# Beacon.net
KiCad netlist of a schematic drawn in Altium Designer
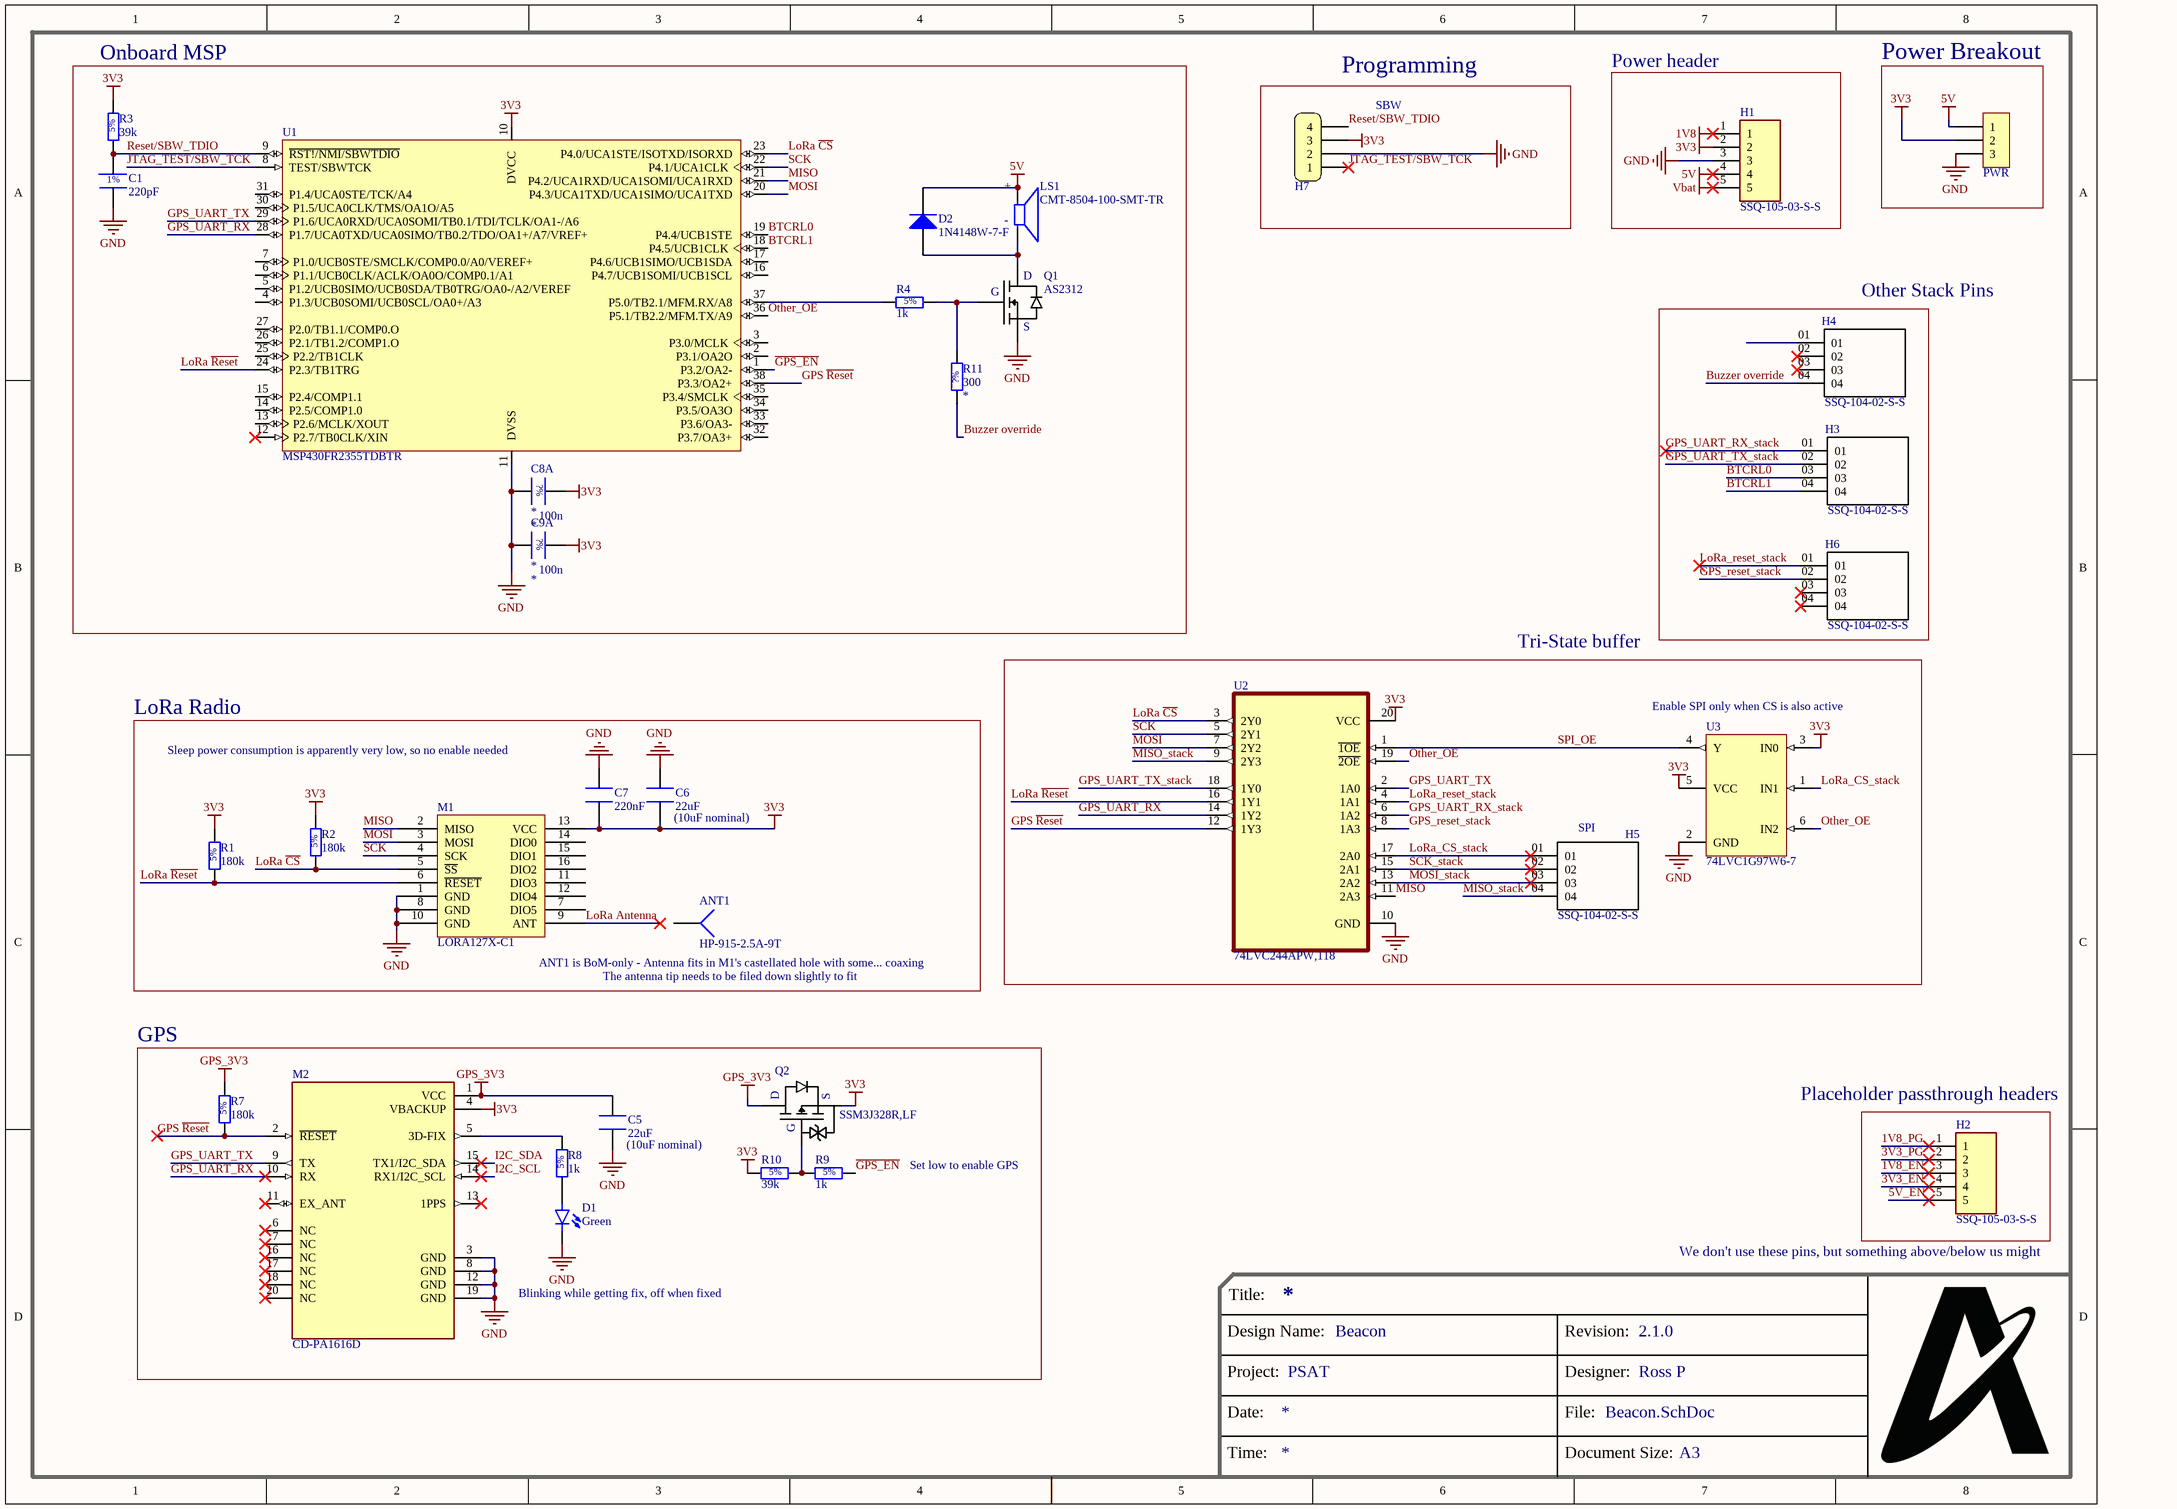
[diagram p0: Beacon.SchDoc]

(export (version "E")
  (design (tool "Eeschema 10.0.6"))
  (components
    (comp (ref "ANT1")
      (value "HP-915-2.5A-9T")
      (description "Spring Antenna")
      (libsource (lib "Miscellaneous Connectors") (part "Socket"))
    )
    (comp (ref "C1")
      (value "220pF")
      (footprint "APSS Prototype Parts:CAPACITOR_0805_2012M-70N")
      (description "Passive - Capacitor Series, C0G, 5pF ~ 22nF, 50V, 0805 (2012 Metric), ±1%, -55°C ~ 125°C")
      (fields (field (name "TOLERANCE") "±1%") (field (name "APSS STANDARD PART") "APSS Standard"))
      (libsource (lib "APSS Prototype Parts") (part "GCM2165CxxxxxF Series"))
    )
    (comp (ref "C5")
      (value "22uF")
      (footprint "APSS Prototype Parts:CAPACITOR_0805_2012M-70N")
      (description "Passive - Capacitor, X5R, 22uF Max, 6.3V, 0805 (2012 Metric), ±20%, -55°C ~ 85°C. 8.8uF @ 5V")
      (fields (field (name "TOLERANCE") "±20%") (field (name "MF PART NO.") "C0805C226M9PACTU"))
      (libsource (lib "APSS Prototype Parts") (part "C0805C226M9PACTU"))
    )
    (comp (ref "C6")
      (value "22uF")
      (footprint "APSS Prototype Parts:CAPACITOR_0805_2012M-70N")
      (description "Passive - Capacitor, X5R, 22uF Max, 6.3V, 0805 (2012 Metric), ±20%, -55°C ~ 85°C. 8.8uF @ 5V")
      (fields (field (name "TOLERANCE") "±20%") (field (name "MF PART NO.") "C0805C226M9PACTU"))
      (libsource (lib "APSS Prototype Parts") (part "C0805C226M9PACTU"))
    )
    (comp (ref "C7")
      (value "220nF")
      (footprint "APSS Prototype Parts:CAPACITOR_0805_2012M-70N")
      (fields
        (field (name "TOLERANCE") "±10%")
        (field (name "MF PART NO.") "C0805C224K1RAC7800")
        (field (name "APSS STANDARD PART") "APSS Standard")
      )
      (libsource (lib "APSS Prototype Parts") (part "C0805C224K1RAC7800"))
    )
    (comp (ref "C8")
      (value "100n")
      (footprint "CAPACITOR_0805_2012M-70N")
      (description "Passive - Capacitor, Generic")
      (fields
        (field (name "TOLERANCE") "?%")
        (field (name "MF PART NO.") "*")
        (field (name "ALTIUM_VALUE") "*")
      )
      (libsource (lib "APSS Generic Components") (part "Generic Capacitor"))
    )
    (comp (ref "C9")
      (value "100n")
      (footprint "CAPACITOR_0805_2012M-70N")
      (description "Passive - Capacitor, Generic")
      (fields
        (field (name "TOLERANCE") "?%")
        (field (name "MF PART NO.") "*")
        (field (name "ALTIUM_VALUE") "*")
      )
      (libsource (lib "APSS Generic Components") (part "Generic Capacitor"))
    )
    (comp (ref "D1")
      (value "LTST-C190 Series")
      (footprint "APSS Prototype Parts:LED_0603_1608M_0.80mm")
      (description "Diode - LED, 0603")
      (fields
        (field (name "MF PART NO.") "LTST-C190KGKT")
        (field (name "COLOUR") "Green")
        (field (name "APSS STANDARD PART") "APSS Standard")
      )
      (libsource (lib "APSS Prototype Parts") (part "LTST-C190 Series"))
    )
    (comp (ref "D2")
      (value "1N4148W-7-F")
      (footprint "SOD123")
      (description "DIODE GEN PURP 100V 300MA SOD123")
      (fields
        (field (name "MANUFACTURER") "Diodes Incorporated")
        (field (name "MANUFACTURER PART NUMBER") "1N4148W-13-F")
      )
      (libsource (lib "EE209_Library") (part "1N4148_SMT_SOD123"))
    )
    (comp (ref "H1")
      (value "SSQ-105-03-S-S")
      (footprint "SAMTEC_SSQ-105-03-S-S:SAMTEC_SSQ-105-03-S-S")
      (libsource (lib "SSQ-105-03-S-S") (part "SSQ-105-03-S-S"))
    )
    (comp (ref "H2")
      (value "SSQ-105-03-S-S")
      (footprint "SAMTEC_SSQ-105-03-S-S:SAMTEC_SSQ-105-03-S-S")
      (libsource (lib "SSQ-105-03-S-S") (part "SSQ-105-03-S-S"))
    )
    (comp (ref "H3")
      (value "SSQ-104-02-S-S")
      (footprint "*SAMTEC_SSQ-104-02-S-S_SSQ-104-02-S-S(Primary)")
      (libsource (lib "SSQ-104-02-S-S") (part "SSQ-104-02-S-S"))
    )
    (comp (ref "H4")
      (value "SSQ-104-02-S-S")
      (footprint "*SAMTEC_SSQ-104-02-S-S_SSQ-104-02-S-S(Primary)")
      (libsource (lib "SSQ-104-02-S-S") (part "SSQ-104-02-S-S"))
    )
    (comp (ref "H5")
      (value "SSQ-104-02-S-S")
      (footprint "*SAMTEC_SSQ-104-02-S-S_SSQ-104-02-S-S(Primary)")
      (libsource (lib "SSQ-104-02-S-S") (part "SSQ-104-02-S-S"))
    )
    (comp (ref "H6")
      (value "SSQ-104-02-S-S")
      (footprint "*SAMTEC_SSQ-104-02-S-S_SSQ-104-02-S-S(Primary)")
      (libsource (lib "SSQ-104-02-S-S") (part "SSQ-104-02-S-S"))
    )
    (comp (ref "H7")
      (value "Headerless Pogo Holes 4-pin")
      (footprint "APSS Generic Components:POGO_4_PIN_HEADER")
      (libsource (lib "APSS Generic Components") (part "Headerless Pogo Holes 4-pin"))
    )
    (comp (ref "LS1")
      (value "CMT-8504-100-SMT-TR")
      (footprint "XDCR_CMT-8504-100-SMT-TR")
      (description "8.5 mm, 5 Vo-p, 100 dB, Surface Mount (SMT), Magnetic Audio Transducer Buzzer")
      (libsource (lib "CMT-8504-100-SMT-TR") (part "CMT-8504-100-SMT-TR"))
    )
    (comp (ref "M1")
      (value "LORA127X-C1")
      (footprint "LoRa127X-C1")
      (description "LoRa transceiver")
      (libsource (lib "LORA127X-C1") (part "LORA127X-C1"))
    )
    (comp (ref "M2")
      (value "CD-PA1616D")
      (footprint "XCVR_CD-PA1616D")
      (description "CD-PA1616D GNSS patch antenna module")
      (libsource (lib "CD-PA1616D") (part "CD-PA1616D"))
    )
    (comp (ref "PWR")
      (value "HDR,2.54mm,1x3")
      (footprint "APSS Connectors:HEADER_2.54MM_1x3PIN")
      (description "Connector - 2.54mm, 1x3-pin")
      (libsource (lib "APSS Connectors") (part "HDR,2.54mm,1x3"))
    )
    (comp (ref "Q1")
      (value "AS2312")
      (footprint "APSS Prototype Parts:SOT23-3N-1.15mm")
      (description "Transistor - MOSFET, N-Channel AS2312")
      (fields (field (name "POWER") "1.2W") (field (name "APSS STANDARD PART") "APSS Standard"))
      (libsource (lib "APSS Prototype Parts") (part "AS2312"))
    )
    (comp (ref "Q2")
      (value "SSM3J328R,LF")
      (footprint "APSS Prototype Parts:SOT23F-3-0.8mm")
      (description "Transistor - MOSFET, P-Channel SSM3J328R,LF")
      (fields (field (name "POWER") "1W") (field (name "APSS STANDARD PART") "APSS Standard"))
      (libsource (lib "APSS Prototype Parts") (part "SSM3J328R,LF"))
    )
    (comp (ref "R1")
      (value "180k")
      (footprint "APSS Prototype Parts:Resistor_0805_2012M-50N")
      (fields
        (field (name "TOLERANCE") "5%")
        (field (name "POWER") "1/8W")
        (field (name "MF PART NO.") "RMCF0805JT180K")
      )
      (libsource (lib "APSS Prototype Parts") (part "RMCF0805JT Series"))
    )
    (comp (ref "R2")
      (value "180k")
      (footprint "APSS Prototype Parts:Resistor_0805_2012M-50N")
      (fields
        (field (name "TOLERANCE") "5%")
        (field (name "POWER") "1/8W")
        (field (name "MF PART NO.") "RMCF0805JT180K")
      )
      (libsource (lib "APSS Prototype Parts") (part "RMCF0805JT Series"))
    )
    (comp (ref "R3")
      (value "39k")
      (footprint "APSS Prototype Parts:Resistor_0805_2012M-50N")
      (fields
        (field (name "TOLERANCE") "5%")
        (field (name "POWER") "1/8W")
        (field (name "MF PART NO.") "RMCF0805JT39K0")
      )
      (libsource (lib "APSS Prototype Parts") (part "RMCF0805JT Series"))
    )
    (comp (ref "R4")
      (value "1k")
      (footprint "APSS Prototype Parts:Resistor_0805_2012M-50N")
      (fields
        (field (name "TOLERANCE") "5%")
        (field (name "POWER") "1/8W")
        (field (name "MF PART NO.") "RMCF0805JT1K00")
      )
      (libsource (lib "") (part "RMCF0805JT Series_1"))
    )
    (comp (ref "R7")
      (value "180k")
      (footprint "APSS Prototype Parts:Resistor_0805_2012M-50N")
      (fields
        (field (name "TOLERANCE") "5%")
        (field (name "POWER") "1/8W")
        (field (name "MF PART NO.") "RMCF0805JT180K")
      )
      (libsource (lib "APSS Prototype Parts") (part "RMCF0805JT Series"))
    )
    (comp (ref "R8")
      (value "1k")
      (footprint "APSS Prototype Parts:Resistor_0805_2012M-50N")
      (fields
        (field (name "TOLERANCE") "5%")
        (field (name "POWER") "1/8W")
        (field (name "MF PART NO.") "RMCF0805JT1K00")
      )
      (libsource (lib "APSS Prototype Parts") (part "RMCF0805JT Series"))
    )
    (comp (ref "R9")
      (value "1k")
      (footprint "APSS Prototype Parts:Resistor_0805_2012M-50N")
      (fields
        (field (name "TOLERANCE") "5%")
        (field (name "POWER") "1/8W")
        (field (name "MF PART NO.") "RMCF0805JT1K00")
      )
      (libsource (lib "") (part "RMCF0805JT Series_1"))
    )
    (comp (ref "R10")
      (value "39k")
      (footprint "APSS Prototype Parts:Resistor_0805_2012M-50N")
      (fields
        (field (name "TOLERANCE") "5%")
        (field (name "POWER") "1/8W")
        (field (name "MF PART NO.") "RMCF0805JT39K0")
      )
      (libsource (lib "") (part "RMCF0805JT Series_1"))
    )
    (comp (ref "R11")
      (value "300")
      (footprint "RESISTOR_0805_2012M-50N")
      (description "Passive - Resistor, Generic")
      (fields (field (name "TOLERANCE") "?%") (field (name "MF PART NO.") "*"))
      (libsource (lib "APSS Generic Components") (part "Generic Resistor"))
    )
    (comp (ref "U1")
      (value "MSP430FR2355TDBTR")
      (footprint "APSS Prototype Parts:TSSOP65P640X120-0.5mm-38N")
      (fields
        (field (name "MF PART NO.") "MSP430FR2355TPT")
        (field (name "APSS STANDARD PART") "APSS Standard")
      )
      (libsource (lib "APSS Prototype Parts") (part "MSP430FR2355TDBTR"))
    )
    (comp (ref "U2")
      (value "74LVC244APW,118")
      (footprint "SOP65P640X110-20N:SOP65P640X110-20N")
      (description "Octal buffer/line driver")
      (fields (field (name "MP") "74LVC244APW-118"))
      (libsource (lib "74LVC244APW,118") (part "74LVC244APW,118"))
    )
    (comp (ref "U3")
      (value "74LVC1G97W6-7")
      (footprint "APSS Prototype Parts:SOT23-6N-1.4mm")
      (description "IC - Multifunction Logic Gate, 1 Circuit, 3 Input, 1.65 - 5.5V, AND, OR, NOT, MUX, SOT-23-6")
      (fields (field (name "APSS STANDARD PART") "APSS Standard"))
      (libsource (lib "APSS Prototype Parts") (part "74LVC1G97W6-7"))
    )
  )
  (nets
    (net (code "1") (name "/1V8_EN") (class "Default")
      (node (ref "H2") (pin "3") (pinfunction "3_3") (pintype "passive+no_connect"))
    )
    (net (code "2") (name "/1V8_PG") (class "Default")
      (node (ref "H2") (pin "1") (pinfunction "1_1") (pintype "passive+no_connect"))
    )
    (net (code "3") (name "/3V3_EN") (class "Default")
      (node (ref "H2") (pin "4") (pinfunction "4_4") (pintype "passive+no_connect"))
    )
    (net (code "4") (name "/3V3_PG") (class "Default")
      (node (ref "H2") (pin "2") (pinfunction "2_2") (pintype "passive+no_connect"))
    )
    (net (code "5") (name "/5V_EN") (class "Default")
      (node (ref "H2") (pin "5") (pinfunction "5_5") (pintype "passive+no_connect"))
    )
    (net (code "7") (name "/BTCRL0") (class "Default")
      (node (ref "H3") (pin "03") (pinfunction "03_03") (pintype "passive"))
      (node (ref "U1") (pin "19") (pinfunction "P4.4/UCB1STE_19") (pintype "bidirectional"))
    )
    (net (code "8") (name "/BTCRL1") (class "Default")
      (node (ref "H3") (pin "04") (pinfunction "04_04") (pintype "passive"))
      (node (ref "U1") (pin "18") (pinfunction "P4.5/UCB1CLK_18") (pintype "bidirectional"))
    )
    (net (code "9") (name "/Buzzer override") (class "Default")
      (node (ref "H4") (pin "04") (pinfunction "04_04") (pintype "passive"))
      (node (ref "R11") (pin "1") (pinfunction "1_1") (pintype "passive"))
    )
    (net (code "10") (name "/GPS ~{Reset}") (class "Default")
      (node (ref "M2") (pin "2") (pinfunction "~{RESET}_2") (pintype "input"))
      (node (ref "R7") (pin "1") (pinfunction "1_1") (pintype "passive"))
      (node (ref "U1") (pin "38") (pinfunction "P3.3/OA2+_38") (pintype "bidirectional"))
      (node (ref "U2") (pin "12") (pinfunction "1Y3_12") (pintype "output"))
    )
    (net (code "11") (name "/GPS_UART_RX") (class "Default")
      (node (ref "M2") (pin "10") (pinfunction "RX_10") (pintype "input"))
      (node (ref "U1") (pin "28") (pinfunction "P1.7/UCA0TXD/UCA0SIMO/TB0.2/TDO/OA1+/A7/VREF+_28") (pintype "bidirectional"))
      (node (ref "U2") (pin "14") (pinfunction "1Y2_14") (pintype "output"))
    )
    (net (code "12") (name "/GPS_UART_RX_stack") (class "Default")
      (node (ref "H3") (pin "01") (pinfunction "01_01") (pintype "passive"))
      (node (ref "U2") (pin "6") (pinfunction "1A2_6") (pintype "input"))
    )
    (net (code "13") (name "/GPS_UART_TX") (class "Default")
      (node (ref "M2") (pin "9") (pinfunction "TX_9") (pintype "output"))
      (node (ref "U1") (pin "29") (pinfunction "P1.6/UCA0RXD/UCA0SOMI/TB0.1/TDI/TCLK/OA1-/A6_29") (pintype "bidirectional"))
      (node (ref "U2") (pin "2") (pinfunction "1A0_2") (pintype "input"))
    )
    (net (code "14") (name "/GPS_UART_TX_stack") (class "Default")
      (node (ref "H3") (pin "02") (pinfunction "02_02") (pintype "passive"))
      (node (ref "U2") (pin "18") (pinfunction "1Y0_18") (pintype "output"))
    )
    (net (code "15") (name "/GPS_reset_stack") (class "Default")
      (node (ref "H6") (pin "02") (pinfunction "02_02") (pintype "passive"))
      (node (ref "U2") (pin "8") (pinfunction "1A3_8") (pintype "input"))
    )
    (net (code "16") (name "/I2C_SCL") (class "Default")
      (node (ref "M2") (pin "14") (pinfunction "RX1/I2C_SCL_14") (pintype "input+no_connect"))
    )
    (net (code "17") (name "/I2C_SDA") (class "Default")
      (node (ref "M2") (pin "15") (pinfunction "TX1/I2C_SDA_15") (pintype "output+no_connect"))
    )
    (net (code "18") (name "/JTAG_TEST{slash}SBW_TCK") (class "Default")
      (node (ref "H7") (pin "1") (pinfunction "1_1") (pintype "passive"))
      (node (ref "U1") (pin "8") (pinfunction "TEST/SBWTCK_8") (pintype "input"))
    )
    (net (code "19") (name "/LoRa Antenna") (class "Default")
      (node (ref "M1") (pin "9") (pinfunction "ANT_9") (pintype "passive+no_connect"))
    )
    (net (code "20") (name "/LoRa ~{CS}") (class "Default")
      (node (ref "M1") (pin "5") (pinfunction "~{SS}_5") (pintype "passive"))
      (node (ref "R2") (pin "1") (pinfunction "1_1") (pintype "passive"))
      (node (ref "U1") (pin "23") (pinfunction "P4.0/UCA1STE/ISOTXD/ISORXD_23") (pintype "bidirectional"))
      (node (ref "U2") (pin "3") (pinfunction "2Y0_3") (pintype "output"))
    )
    (net (code "21") (name "/LoRa ~{Reset}") (class "Default")
      (node (ref "M1") (pin "6") (pinfunction "~{RESET}_6") (pintype "passive"))
      (node (ref "R1") (pin "1") (pinfunction "1_1") (pintype "passive"))
      (node (ref "U1") (pin "24") (pinfunction "P2.3/TB1TRG_24") (pintype "bidirectional"))
      (node (ref "U2") (pin "16") (pinfunction "1Y1_16") (pintype "output"))
    )
    (net (code "22") (name "/LoRa_CS_stack") (class "Default")
      (node (ref "H5") (pin "01") (pinfunction "01_01") (pintype "passive"))
      (node (ref "U2") (pin "17") (pinfunction "2A0_17") (pintype "input"))
      (node (ref "U3") (pin "1") (pinfunction "IN1_1") (pintype "input"))
    )
    (net (code "23") (name "/LoRa_reset_stack") (class "Default")
      (node (ref "H6") (pin "01") (pinfunction "01_01") (pintype "passive"))
      (node (ref "U2") (pin "4") (pinfunction "1A1_4") (pintype "input"))
    )
    (net (code "24") (name "/MISO") (class "Default")
      (node (ref "M1") (pin "2") (pinfunction "MISO_2") (pintype "passive"))
      (node (ref "U1") (pin "21") (pinfunction "P4.2/UCA1RXD/UCA1SOMI/UCA1RXD_21") (pintype "bidirectional"))
      (node (ref "U2") (pin "11") (pinfunction "2A3_11") (pintype "input"))
    )
    (net (code "25") (name "/MISO_stack") (class "Default")
      (node (ref "H5") (pin "04") (pinfunction "04_04") (pintype "passive"))
      (node (ref "U2") (pin "9") (pinfunction "2Y3_9") (pintype "output"))
    )
    (net (code "26") (name "/MOSI") (class "Default")
      (node (ref "M1") (pin "3") (pinfunction "MOSI_3") (pintype "passive"))
      (node (ref "U1") (pin "20") (pinfunction "P4.3/UCA1TXD/UCA1SIMO/UCA1TXD_20") (pintype "bidirectional"))
      (node (ref "U2") (pin "7") (pinfunction "2Y2_7") (pintype "output"))
    )
    (net (code "27") (name "/MOSI_stack") (class "Default")
      (node (ref "H5") (pin "03") (pinfunction "03_03") (pintype "passive"))
      (node (ref "U2") (pin "13") (pinfunction "2A2_13") (pintype "input"))
    )
    (net (code "28") (name "/Other_OE") (class "Default")
      (node (ref "U1") (pin "36") (pinfunction "P5.1/TB2.2/MFM.TX/A9_36") (pintype "bidirectional"))
      (node (ref "U2") (pin "19") (pinfunction "~{2OE}_19") (pintype "input"))
      (node (ref "U3") (pin "6") (pinfunction "IN2_6") (pintype "input"))
    )
    (net (code "29") (name "/Reset{slash}SBW_TDIO") (class "Default")
      (node (ref "C1") (pin "2") (pinfunction "2_2") (pintype "passive"))
      (node (ref "H7") (pin "4") (pinfunction "4_4") (pintype "passive"))
      (node (ref "R3") (pin "1") (pinfunction "1_1") (pintype "passive"))
      (node (ref "U1") (pin "9") (pinfunction "~{RST!/NMI/SBWTDIO}_9") (pintype "bidirectional"))
    )
    (net (code "30") (name "/SCK") (class "Default")
      (node (ref "M1") (pin "4") (pinfunction "SCK_4") (pintype "passive"))
      (node (ref "U1") (pin "22") (pinfunction "P4.1/UCA1CLK_22") (pintype "bidirectional"))
      (node (ref "U2") (pin "5") (pinfunction "2Y1_5") (pintype "output"))
    )
    (net (code "31") (name "/SCK_stack") (class "Default")
      (node (ref "H5") (pin "02") (pinfunction "02_02") (pintype "passive"))
      (node (ref "U2") (pin "15") (pinfunction "2A1_15") (pintype "input"))
    )
    (net (code "32") (name "/SPI_OE") (class "Default")
      (node (ref "U2") (pin "1") (pinfunction "~{1OE}_1") (pintype "input"))
      (node (ref "U3") (pin "4") (pinfunction "Y_4") (pintype "output"))
    )
    (net (code "33") (name "/~{GPS_EN}") (class "Default")
      (node (ref "R9") (pin "2") (pinfunction "2_2") (pintype "passive"))
      (node (ref "U1") (pin "1") (pinfunction "P3.2/OA2-_1") (pintype "bidirectional"))
    )
    (net (code "34") (name "1V8") (class "Default")
      (node (ref "H1") (pin "1") (pinfunction "1_1") (pintype "passive"))
    )
    (net (code "35") (name "3V3") (class "Default")
      (node (ref "C6") (pin "1") (pinfunction "1_1") (pintype "passive"))
      (node (ref "C7") (pin "1") (pinfunction "1_1") (pintype "passive"))
      (node (ref "C8") (pin "2") (pinfunction "2_2") (pintype "passive"))
      (node (ref "C9") (pin "2") (pinfunction "2_2") (pintype "passive"))
      (node (ref "H1") (pin "2") (pinfunction "2_2") (pintype "passive"))
      (node (ref "H7") (pin "3") (pinfunction "3_3") (pintype "passive"))
      (node (ref "M1") (pin "13") (pinfunction "VCC_13") (pintype "passive"))
      (node (ref "M2") (pin "4") (pinfunction "VBACKUP_4") (pintype "power_in"))
      (node (ref "PWR") (pin "2") (pinfunction "2_2") (pintype "passive"))
      (node (ref "Q2") (pin "2") (pinfunction "S_2") (pintype "passive"))
      (node (ref "R1") (pin "2") (pinfunction "2_2") (pintype "passive"))
      (node (ref "R10") (pin "1") (pinfunction "1_1") (pintype "passive"))
      (node (ref "R2") (pin "2") (pinfunction "2_2") (pintype "passive"))
      (node (ref "R3") (pin "2") (pinfunction "2_2") (pintype "passive"))
      (node (ref "U1") (pin "10") (pinfunction "DVCC_10") (pintype "power_in"))
      (node (ref "U2") (pin "20") (pinfunction "VCC_20") (pintype "power_in"))
      (node (ref "U3") (pin "3") (pinfunction "IN0_3") (pintype "input"))
      (node (ref "U3") (pin "5") (pinfunction "VCC_5") (pintype "power_in"))
    )
    (net (code "36") (name "5V") (class "Default")
      (node (ref "D2") (pin "2") (pinfunction "K_2") (pintype "passive"))
      (node (ref "H1") (pin "4") (pinfunction "4_4") (pintype "passive"))
      (node (ref "LS1") (pin "P") (pinfunction "P_P") (pintype "passive"))
      (node (ref "PWR") (pin "1") (pinfunction "1_1") (pintype "passive"))
    )
    (net (code "37") (name "GND") (class "Default")
      (node (ref "C1") (pin "1") (pinfunction "1_1") (pintype "passive"))
      (node (ref "C5") (pin "1") (pinfunction "1_1") (pintype "passive"))
      (node (ref "C6") (pin "2") (pinfunction "2_2") (pintype "passive"))
      (node (ref "C7") (pin "2") (pinfunction "2_2") (pintype "passive"))
      (node (ref "C8") (pin "1") (pinfunction "1_1") (pintype "passive"))
      (node (ref "C9") (pin "1") (pinfunction "1_1") (pintype "passive"))
      (node (ref "D1") (pin "C") (pinfunction "C_C") (pintype "passive"))
      (node (ref "H1") (pin "3") (pinfunction "3_3") (pintype "passive"))
      (node (ref "H7") (pin "2") (pinfunction "2_2") (pintype "passive"))
      (node (ref "M1") (pin "1") (pinfunction "GND_1") (pintype "passive"))
      (node (ref "M1") (pin "10") (pinfunction "GND_10") (pintype "passive"))
      (node (ref "M1") (pin "8") (pinfunction "GND_8") (pintype "passive"))
      (node (ref "M2") (pin "12") (pinfunction "GND_12") (pintype "power_in"))
      (node (ref "M2") (pin "19") (pinfunction "GND_19") (pintype "power_in"))
      (node (ref "M2") (pin "3") (pinfunction "GND_3") (pintype "power_in"))
      (node (ref "M2") (pin "8") (pinfunction "GND_8") (pintype "power_in"))
      (node (ref "PWR") (pin "3") (pinfunction "3_3") (pintype "passive"))
      (node (ref "Q1") (pin "2") (pinfunction "S_2") (pintype "passive"))
      (node (ref "U1") (pin "11") (pinfunction "DVSS_11") (pintype "power_in"))
      (node (ref "U2") (pin "10") (pinfunction "GND_10") (pintype "passive"))
      (node (ref "U3") (pin "2") (pinfunction "GND_2") (pintype "passive"))
    )
    (net (code "38") (name "GPS_3V3") (class "Default")
      (node (ref "C5") (pin "2") (pinfunction "2_2") (pintype "passive"))
      (node (ref "M2") (pin "1") (pinfunction "VCC_1") (pintype "power_in"))
      (node (ref "Q2") (pin "3") (pinfunction "D_3") (pintype "passive"))
      (node (ref "R7") (pin "2") (pinfunction "2_2") (pintype "passive"))
    )
    (net (code "39") (name "Net-(D1-PadA)") (class "Default")
      (node (ref "D1") (pin "A") (pinfunction "A_A") (pintype "passive"))
      (node (ref "R8") (pin "1") (pinfunction "1_1") (pintype "passive"))
    )
    (net (code "40") (name "Net-(D2-A)") (class "Default")
      (node (ref "D2") (pin "1") (pinfunction "A_1") (pintype "passive"))
      (node (ref "LS1") (pin "N") (pinfunction "N_N") (pintype "passive"))
      (node (ref "Q1") (pin "3") (pinfunction "D_3") (pintype "passive"))
    )
    (net (code "41") (name "Net-(M2-3D-FIX)") (class "Default")
      (node (ref "M2") (pin "5") (pinfunction "3D-FIX_5") (pintype "output"))
      (node (ref "R8") (pin "2") (pinfunction "2_2") (pintype "passive"))
    )
    (net (code "42") (name "Net-(Q1-G)") (class "Default")
      (node (ref "Q1") (pin "1") (pinfunction "G_1") (pintype "passive"))
      (node (ref "R11") (pin "2") (pinfunction "2_2") (pintype "passive"))
      (node (ref "R4") (pin "2") (pinfunction "2_2") (pintype "passive"))
    )
    (net (code "43") (name "Net-(Q2-G)") (class "Default")
      (node (ref "Q2") (pin "1") (pinfunction "G_1") (pintype "passive"))
      (node (ref "R10") (pin "2") (pinfunction "2_2") (pintype "passive"))
      (node (ref "R9") (pin "1") (pinfunction "1_1") (pintype "passive"))
    )
    (net (code "44") (name "Net-(U1-P5.0{slash}TB2.1{slash}MFM.RX{slash}A8)") (class "Default")
      (node (ref "R4") (pin "1") (pinfunction "1_1") (pintype "passive"))
      (node (ref "U1") (pin "37") (pinfunction "P5.0/TB2.1/MFM.RX/A8_37") (pintype "bidirectional"))
    )
    (net (code "45") (name "Vbat") (class "Default")
      (node (ref "H1") (pin "5") (pinfunction "5_5") (pintype "passive"))
    )
    (net (code "46") (name "unconnected-(ANT1-Pad1)") (class "Default")
      (node (ref "ANT1") (pin "1") (pinfunction "1_1") (pintype "passive"))
    )
    (net (code "47") (name "unconnected-(H4-Pad01)") (class "Default")
      (node (ref "H4") (pin "01") (pinfunction "01_01") (pintype "passive"))
    )
    (net (code "48") (name "unconnected-(H4-Pad02)") (class "Default")
      (node (ref "H4") (pin "02") (pinfunction "02_02") (pintype "passive+no_connect"))
    )
    (net (code "49") (name "unconnected-(H4-Pad03)") (class "Default")
      (node (ref "H4") (pin "03") (pinfunction "03_03") (pintype "passive+no_connect"))
    )
    (net (code "50") (name "unconnected-(H6-Pad03)") (class "Default")
      (node (ref "H6") (pin "03") (pinfunction "03_03") (pintype "passive+no_connect"))
    )
    (net (code "51") (name "unconnected-(H6-Pad04)") (class "Default")
      (node (ref "H6") (pin "04") (pinfunction "04_04") (pintype "passive+no_connect"))
    )
    (net (code "52") (name "unconnected-(M1-DIO0-Pad14)") (class "Default")
      (node (ref "M1") (pin "14") (pinfunction "DIO0_14") (pintype "passive"))
    )
    (net (code "53") (name "unconnected-(M1-DIO1-Pad15)") (class "Default")
      (node (ref "M1") (pin "15") (pinfunction "DIO1_15") (pintype "passive"))
    )
    (net (code "54") (name "unconnected-(M1-DIO2-Pad16)") (class "Default")
      (node (ref "M1") (pin "16") (pinfunction "DIO2_16") (pintype "passive"))
    )
    (net (code "55") (name "unconnected-(M1-DIO3-Pad11)") (class "Default")
      (node (ref "M1") (pin "11") (pinfunction "DIO3_11") (pintype "passive"))
    )
    (net (code "56") (name "unconnected-(M1-DIO4-Pad12)") (class "Default")
      (node (ref "M1") (pin "12") (pinfunction "DIO4_12") (pintype "passive"))
    )
    (net (code "57") (name "unconnected-(M1-DIO5-Pad7)") (class "Default")
      (node (ref "M1") (pin "7") (pinfunction "DIO5_7") (pintype "passive"))
    )
    (net (code "58") (name "unconnected-(M2-1PPS-Pad13)") (class "Default")
      (node (ref "M2") (pin "13") (pinfunction "1PPS_13") (pintype "output+no_connect"))
    )
    (net (code "59") (name "unconnected-(M2-EX_ANT-Pad11)") (class "Default")
      (node (ref "M2") (pin "11") (pinfunction "EX_ANT_11") (pintype "bidirectional+no_connect"))
    )
    (net (code "60") (name "unconnected-(M2-NC-Pad6)") (class "Default")
      (node (ref "M2") (pin "6") (pinfunction "NC_6") (pintype "passive+no_connect"))
    )
    (net (code "61") (name "unconnected-(M2-NC-Pad7)") (class "Default")
      (node (ref "M2") (pin "7") (pinfunction "NC_7") (pintype "passive+no_connect"))
    )
    (net (code "62") (name "unconnected-(M2-NC-Pad16)") (class "Default")
      (node (ref "M2") (pin "16") (pinfunction "NC_16") (pintype "passive+no_connect"))
    )
    (net (code "63") (name "unconnected-(M2-NC-Pad17)") (class "Default")
      (node (ref "M2") (pin "17") (pinfunction "NC_17") (pintype "passive+no_connect"))
    )
    (net (code "64") (name "unconnected-(M2-NC-Pad18)") (class "Default")
      (node (ref "M2") (pin "18") (pinfunction "NC_18") (pintype "passive+no_connect"))
    )
    (net (code "65") (name "unconnected-(M2-NC-Pad20)") (class "Default")
      (node (ref "M2") (pin "20") (pinfunction "NC_20") (pintype "passive+no_connect"))
    )
    (net (code "66") (name "unconnected-(U1-P1.0{slash}UCB0STE{slash}SMCLK{slash}COMP0.0{slash}A0{slash}VEREF+-Pad7)") (class "Default")
      (node (ref "U1") (pin "7") (pinfunction "P1.0/UCB0STE/SMCLK/COMP0.0/A0/VEREF+_7") (pintype "bidirectional"))
    )
    (net (code "67") (name "unconnected-(U1-P1.1{slash}UCB0CLK{slash}ACLK{slash}OA0O{slash}COMP0.1{slash}A1-Pad6)") (class "Default")
      (node (ref "U1") (pin "6") (pinfunction "P1.1/UCB0CLK/ACLK/OA0O/COMP0.1/A1_6") (pintype "bidirectional"))
    )
    (net (code "68") (name "unconnected-(U1-P1.2{slash}UCB0SIMO{slash}UCB0SDA{slash}TB0TRG{slash}OA0-{slash}A2{slash}VEREF-Pad5)") (class "Default")
      (node (ref "U1") (pin "5") (pinfunction "P1.2/UCB0SIMO/UCB0SDA/TB0TRG/OA0-/A2/VEREF_5") (pintype "bidirectional"))
    )
    (net (code "69") (name "unconnected-(U1-P1.3{slash}UCB0SOMI{slash}UCB0SCL{slash}OA0+{slash}A3-Pad4)") (class "Default")
      (node (ref "U1") (pin "4") (pinfunction "P1.3/UCB0SOMI/UCB0SCL/OA0+/A3_4") (pintype "bidirectional"))
    )
    (net (code "70") (name "unconnected-(U1-P1.4{slash}UCA0STE{slash}TCK{slash}A4-Pad31)") (class "Default")
      (node (ref "U1") (pin "31") (pinfunction "P1.4/UCA0STE/TCK/A4_31") (pintype "bidirectional"))
    )
    (net (code "71") (name "unconnected-(U1-P1.5{slash}UCA0CLK{slash}TMS{slash}OA1O{slash}A5-Pad30)") (class "Default")
      (node (ref "U1") (pin "30") (pinfunction "P1.5/UCA0CLK/TMS/OA1O/A5_30") (pintype "bidirectional"))
    )
    (net (code "72") (name "unconnected-(U1-P2.0{slash}TB1.1{slash}COMP0.O-Pad27)") (class "Default")
      (node (ref "U1") (pin "27") (pinfunction "P2.0/TB1.1/COMP0.O_27") (pintype "bidirectional"))
    )
    (net (code "73") (name "unconnected-(U1-P2.1{slash}TB1.2{slash}COMP1.O-Pad26)") (class "Default")
      (node (ref "U1") (pin "26") (pinfunction "P2.1/TB1.2/COMP1.O_26") (pintype "bidirectional"))
    )
    (net (code "74") (name "unconnected-(U1-P2.2{slash}TB1CLK-Pad25)") (class "Default")
      (node (ref "U1") (pin "25") (pinfunction "P2.2/TB1CLK_25") (pintype "bidirectional"))
    )
    (net (code "75") (name "unconnected-(U1-P2.4{slash}COMP1.1-Pad15)") (class "Default")
      (node (ref "U1") (pin "15") (pinfunction "P2.4/COMP1.1_15") (pintype "bidirectional"))
    )
    (net (code "76") (name "unconnected-(U1-P2.5{slash}COMP1.0-Pad14)") (class "Default")
      (node (ref "U1") (pin "14") (pinfunction "P2.5/COMP1.0_14") (pintype "bidirectional"))
    )
    (net (code "77") (name "unconnected-(U1-P2.6{slash}MCLK{slash}XOUT-Pad13)") (class "Default")
      (node (ref "U1") (pin "13") (pinfunction "P2.6/MCLK/XOUT_13") (pintype "bidirectional"))
    )
    (net (code "78") (name "unconnected-(U1-P2.7{slash}TB0CLK{slash}XIN-Pad12)") (class "Default")
      (node (ref "U1") (pin "12") (pinfunction "P2.7/TB0CLK/XIN_12") (pintype "input+no_connect"))
    )
    (net (code "79") (name "unconnected-(U1-P3.0{slash}MCLK-Pad3)") (class "Default")
      (node (ref "U1") (pin "3") (pinfunction "P3.0/MCLK_3") (pintype "bidirectional"))
    )
    (net (code "80") (name "unconnected-(U1-P3.1{slash}OA2O-Pad2)") (class "Default")
      (node (ref "U1") (pin "2") (pinfunction "P3.1/OA2O_2") (pintype "bidirectional"))
    )
    (net (code "81") (name "unconnected-(U1-P3.4{slash}SMCLK-Pad35)") (class "Default")
      (node (ref "U1") (pin "35") (pinfunction "P3.4/SMCLK_35") (pintype "bidirectional"))
    )
    (net (code "82") (name "unconnected-(U1-P3.5{slash}OA3O-Pad34)") (class "Default")
      (node (ref "U1") (pin "34") (pinfunction "P3.5/OA3O_34") (pintype "bidirectional"))
    )
    (net (code "83") (name "unconnected-(U1-P3.6{slash}OA3--Pad33)") (class "Default")
      (node (ref "U1") (pin "33") (pinfunction "P3.6/OA3-_33") (pintype "bidirectional"))
    )
    (net (code "84") (name "unconnected-(U1-P3.7{slash}OA3+-Pad32)") (class "Default")
      (node (ref "U1") (pin "32") (pinfunction "P3.7/OA3+_32") (pintype "bidirectional"))
    )
    (net (code "85") (name "unconnected-(U1-P4.6{slash}UCB1SIMO{slash}UCB1SDA-Pad17)") (class "Default")
      (node (ref "U1") (pin "17") (pinfunction "P4.6/UCB1SIMO/UCB1SDA_17") (pintype "bidirectional"))
    )
    (net (code "86") (name "unconnected-(U1-P4.7{slash}UCB1SOMI{slash}UCB1SCL-Pad16)") (class "Default")
      (node (ref "U1") (pin "16") (pinfunction "P4.7/UCB1SOMI/UCB1SCL_16") (pintype "bidirectional"))
    )
  )
)
